# DAU_Kupplung_1_phasig_V1_13.net
KiCad netlist of a schematic drawn in EAGLE
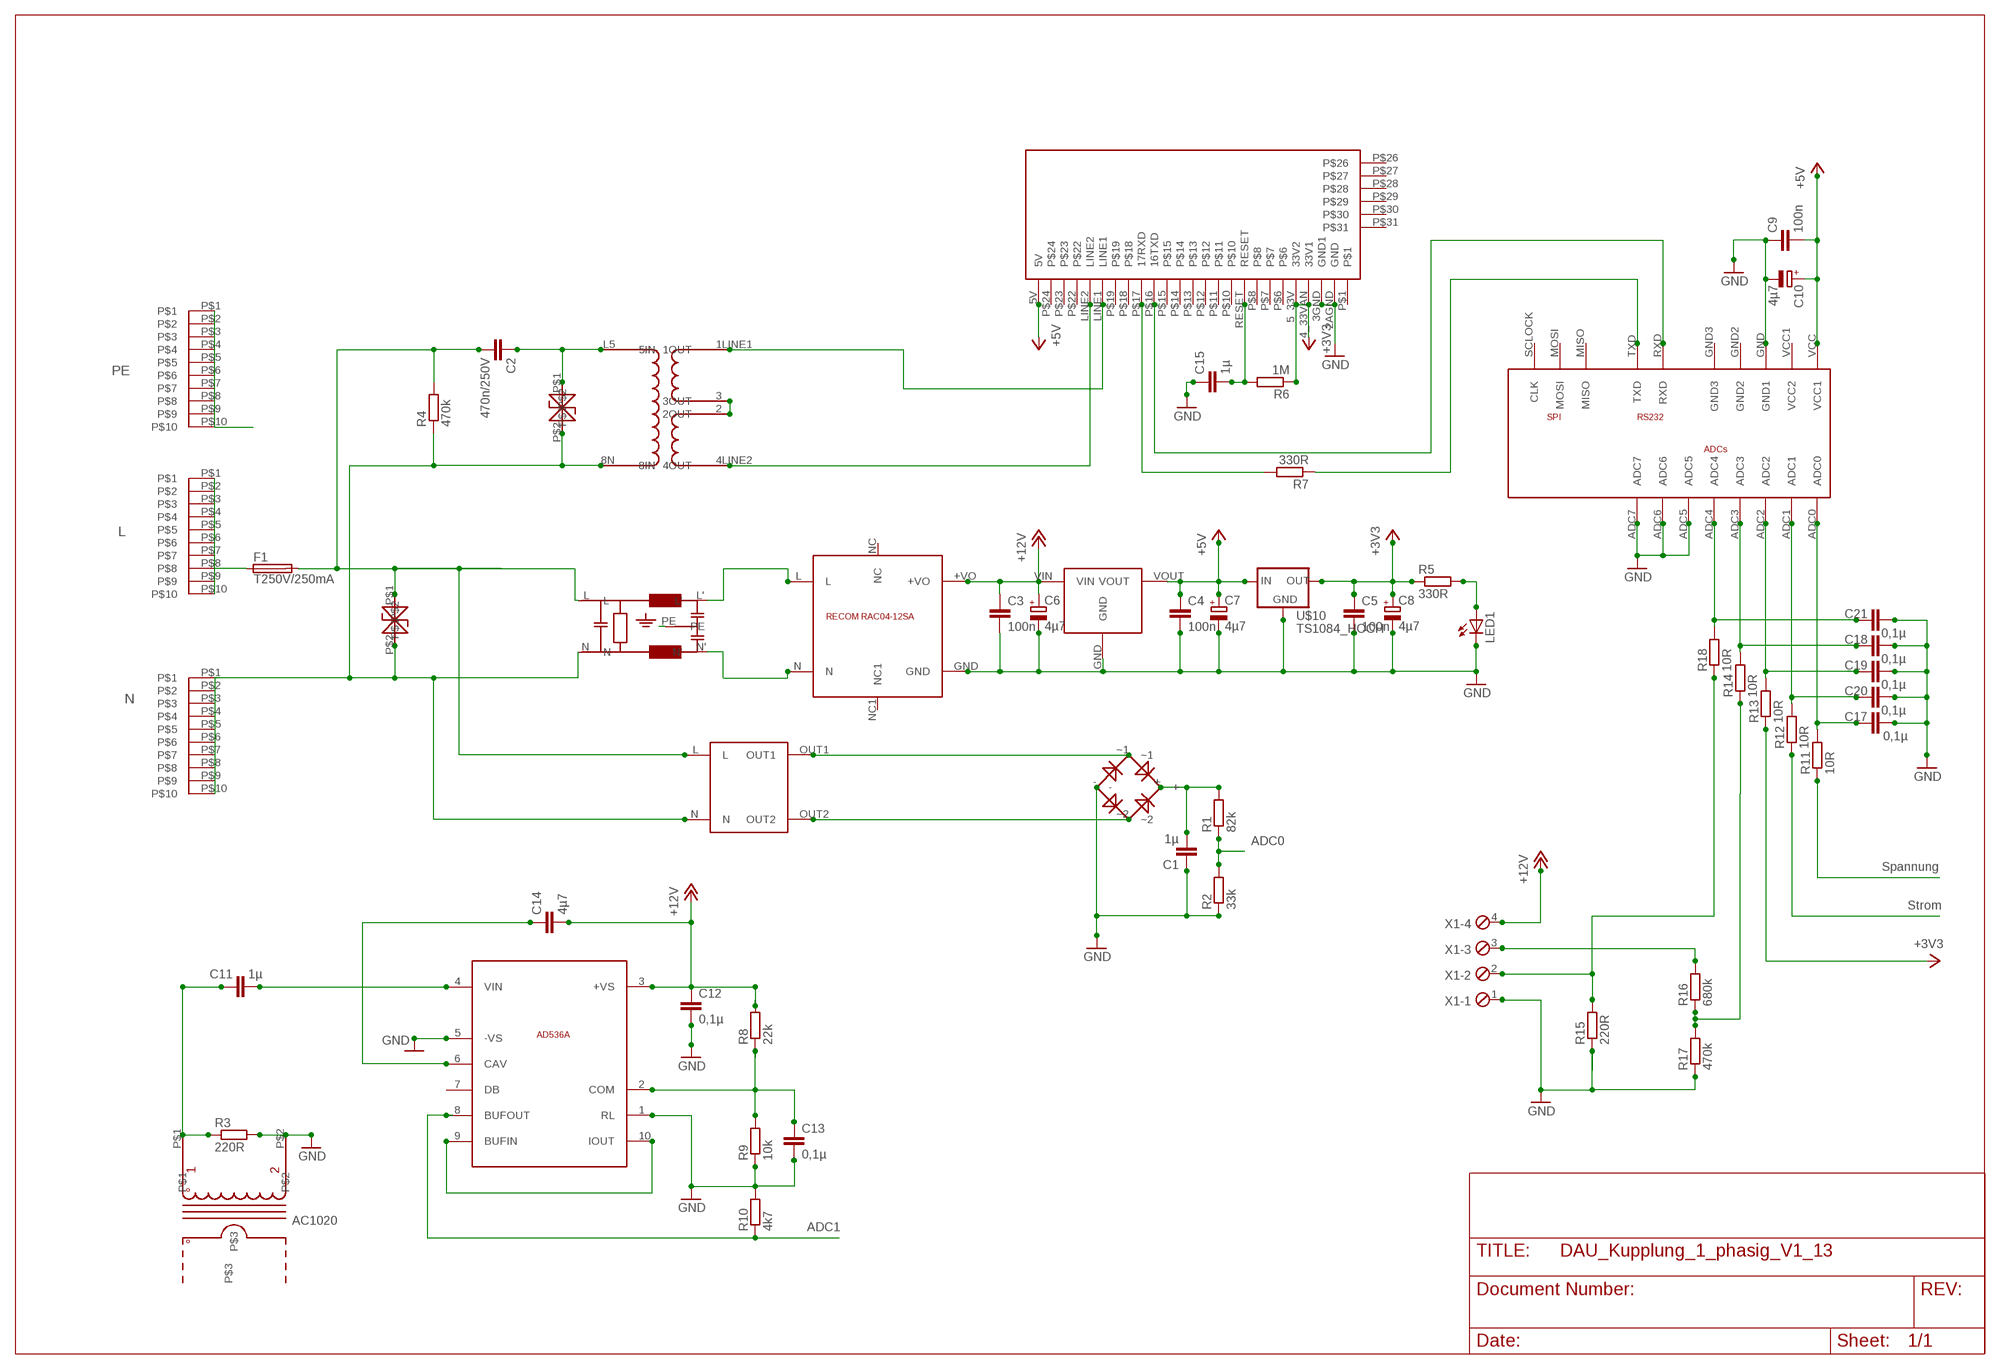
[diagram p0: schematic, sheet 1]

(export (version "E")
  (design (tool "Eeschema 10.0.6"))
  (components
    (comp (ref "AC1020")
      (value "AC1010")
      (footprint "eagle-import:AC1010")
      (libsource (lib "eagle-import") (part "AC1010"))
    )
    (comp (ref "C1")
      (value "1µ")
      (footprint "eagle-import:C2.5-3")
      (libsource (lib "eagle-import") (part "C2,5-3"))
    )
    (comp (ref "C2")
      (value "470n/250V")
      (footprint "eagle-import:C150-072X183")
      (libsource (lib "eagle-import") (part "resistor_C-EU150-072X183"))
    )
    (comp (ref "C3")
      (value "100n")
      (footprint "eagle-import:C0805")
      (libsource (lib "eagle-import") (part "resistor_C-EUC0805"))
    )
    (comp (ref "C4")
      (value "100n")
      (footprint "eagle-import:C0805")
      (libsource (lib "eagle-import") (part "resistor_C-EUC0805"))
    )
    (comp (ref "C5")
      (value "100n")
      (footprint "eagle-import:C0805")
      (libsource (lib "eagle-import") (part "resistor_C-EUC0805"))
    )
    (comp (ref "C6")
      (value "4µ7")
      (footprint "eagle-import:E2-4")
      (libsource (lib "eagle-import") (part "CPOL-EUE2-4"))
    )
    (comp (ref "C7")
      (value "4µ7")
      (footprint "eagle-import:E2-4")
      (libsource (lib "eagle-import") (part "CPOL-EUE2-4"))
    )
    (comp (ref "C8")
      (value "4µ7")
      (footprint "eagle-import:E2-4")
      (libsource (lib "eagle-import") (part "CPOL-EUE2-4"))
    )
    (comp (ref "C9")
      (value "100n")
      (footprint "eagle-import:C0805")
      (libsource (lib "eagle-import") (part "C-EUC0805"))
    )
    (comp (ref "C10")
      (value "4µ7")
      (footprint "eagle-import:E2-4")
      (libsource (lib "eagle-import") (part "CPOL-EUE2-4"))
    )
    (comp (ref "C11")
      (value "1µ")
      (footprint "eagle-import:C0805")
      (libsource (lib "eagle-import") (part "C-EUC0805"))
    )
    (comp (ref "C12")
      (value "0,1µ")
      (footprint "eagle-import:C0805")
      (libsource (lib "eagle-import") (part "C-EUC0805"))
    )
    (comp (ref "C13")
      (value "0,1µ")
      (footprint "eagle-import:C0805")
      (libsource (lib "eagle-import") (part "C-EUC0805"))
    )
    (comp (ref "C14")
      (value "4µ7")
      (footprint "eagle-import:C0805")
      (libsource (lib "eagle-import") (part "C-EUC0805"))
    )
    (comp (ref "C15")
      (value "1µ")
      (footprint "eagle-import:C0805")
      (libsource (lib "eagle-import") (part "resistor_C-EUC0805"))
    )
    (comp (ref "C17")
      (value "0,1µ")
      (footprint "eagle-import:C0805")
      (libsource (lib "eagle-import") (part "resistor_C-EUC0805"))
    )
    (comp (ref "C18")
      (value "0,1µ")
      (footprint "eagle-import:C0805")
      (libsource (lib "eagle-import") (part "resistor_C-EUC0805"))
    )
    (comp (ref "C19")
      (value "0,1µ")
      (footprint "eagle-import:C0805")
      (libsource (lib "eagle-import") (part "resistor_C-EUC0805"))
    )
    (comp (ref "C20")
      (value "0,1µ")
      (footprint "eagle-import:C0805")
      (libsource (lib "eagle-import") (part "resistor_C-EUC0805"))
    )
    (comp (ref "C21")
      (value "0,1µ")
      (footprint "eagle-import:C0805")
      (libsource (lib "eagle-import") (part "resistor_C-EUC0805"))
    )
    (comp (ref "F1")
      (value "T250V/250mA")
      (footprint "eagle-import:TR5")
      (libsource (lib "eagle-import") (part "TR5"))
    )
    (comp (ref "L")
      (value "PRINT_CONNECTOR")
      (footprint "eagle-import:FASTON_DOUBLE")
      (libsource (lib "eagle-import") (part "PRINT_CONNECTOR"))
    )
    (comp (ref "LED1")
      (value "LEDSQR2X5")
      (footprint "eagle-import:LED2X5")
      (libsource (lib "eagle-import") (part "LEDSQR2X5"))
    )
    (comp (ref "N")
      (value "PRINT_CONNECTOR")
      (footprint "eagle-import:FASTON_DOUBLE")
      (libsource (lib "eagle-import") (part "PRINT_CONNECTOR"))
    )
    (comp (ref "PE")
      (value "PRINT_CONNECTOR")
      (footprint "eagle-import:FASTON_DOUBLE")
      (libsource (lib "eagle-import") (part "PRINT_CONNECTOR"))
    )
    (comp (ref "R1")
      (value "82k")
      (footprint "eagle-import:R1206")
      (libsource (lib "eagle-import") (part "R-EU_R1206"))
    )
    (comp (ref "R2")
      (value "33k")
      (footprint "eagle-import:R1206")
      (libsource (lib "eagle-import") (part "R-EU_R1206"))
    )
    (comp (ref "R3")
      (value "220R")
      (footprint "eagle-import:R1206")
      (libsource (lib "eagle-import") (part "R-EU_R1206"))
    )
    (comp (ref "R4")
      (value "470k")
      (footprint "eagle-import:0204_7")
      (libsource (lib "eagle-import") (part "R-EU_0204/7"))
    )
    (comp (ref "R5")
      (value "330R")
      (footprint "eagle-import:R1206")
      (libsource (lib "eagle-import") (part "R-EU_R1206"))
    )
    (comp (ref "R6")
      (value "1M")
      (footprint "eagle-import:R1206")
      (libsource (lib "eagle-import") (part "R-EU_R1206"))
    )
    (comp (ref "R7")
      (value "330R")
      (footprint "eagle-import:R1206")
      (libsource (lib "eagle-import") (part "R-EU_R1206"))
    )
    (comp (ref "R8")
      (value "22k")
      (footprint "eagle-import:R1206")
      (libsource (lib "eagle-import") (part "R-EU_R1206"))
    )
    (comp (ref "R9")
      (value "10k")
      (footprint "eagle-import:R1206")
      (libsource (lib "eagle-import") (part "R-EU_R1206"))
    )
    (comp (ref "R10")
      (value "4k7")
      (footprint "eagle-import:R1206")
      (libsource (lib "eagle-import") (part "R-EU_R1206"))
    )
    (comp (ref "R11")
      (value "10R")
      (footprint "eagle-import:R1206")
      (libsource (lib "eagle-import") (part "R-EU_R1206"))
    )
    (comp (ref "R12")
      (value "10R")
      (footprint "eagle-import:R1206")
      (libsource (lib "eagle-import") (part "R-EU_R1206"))
    )
    (comp (ref "R13")
      (value "10R")
      (footprint "eagle-import:R1206")
      (libsource (lib "eagle-import") (part "R-EU_R1206"))
    )
    (comp (ref "R14")
      (value "10R")
      (footprint "eagle-import:R1206")
      (libsource (lib "eagle-import") (part "R-EU_R1206"))
    )
    (comp (ref "R15")
      (value "220R")
      (footprint "eagle-import:R1206")
      (libsource (lib "eagle-import") (part "R-EU_R1206"))
    )
    (comp (ref "R16")
      (value "680k")
      (footprint "eagle-import:R1206")
      (libsource (lib "eagle-import") (part "R-EU_R1206"))
    )
    (comp (ref "R17")
      (value "470k")
      (footprint "eagle-import:R1206")
      (libsource (lib "eagle-import") (part "R-EU_R1206"))
    )
    (comp (ref "R18")
      (value "10R")
      (footprint "eagle-import:R1206")
      (libsource (lib "eagle-import") (part "R-EU_R1206"))
    )
    (comp (ref "U$1")
      (value "RECOM_RAC04_12SA")
      (footprint "eagle-import:RAC04_12SA")
      (libsource (lib "eagle-import") (part "RECOM_RAC04_12SA"))
    )
    (comp (ref "U$2")
      (value "SICHERHEITSTRAFO")
      (footprint "eagle-import:TRAFO_0,35VA")
      (libsource (lib "eagle-import") (part "SICHERHEITSTRAFO"))
    )
    (comp (ref "U$3")
      (value "ADUC831_MINIMUM")
      (footprint "eagle-import:ADUC_MINIMUM")
      (libsource (lib "eagle-import") (part "ADUC831_MINIMUM"))
    )
    (comp (ref "U$4")
      (value "IT800")
      (footprint "eagle-import:IT800")
      (libsource (lib "eagle-import") (part "IT800"))
    )
    (comp (ref "U$5")
      (value "PLC_UEBERTRAGER_V2")
      (footprint "eagle-import:PLC-UEBERTRAGER_V2")
      (libsource (lib "eagle-import") (part "PLC_UEBERTRAGER_V2"))
    )
    (comp (ref "U$6")
      (value "NETZFILTER_05_A")
      (footprint "eagle-import:NETZFILTER")
      (libsource (lib "eagle-import") (part "NETZFILTER_05_A"))
    )
    (comp (ref "U$7")
      (value "AD536")
      (footprint "eagle-import:TO100_10PIN")
      (libsource (lib "eagle-import") (part "AD536"))
    )
    (comp (ref "U$8")
      (value "RECTIFIER")
      (footprint "eagle-import:RECTIFIER")
      (libsource (lib "eagle-import") (part "RECTIFIER"))
    )
    (comp (ref "U$9")
      (value "TSV")
      (footprint "eagle-import:TSV")
      (libsource (lib "eagle-import") (part "TSV"))
    )
    (comp (ref "U$10")
      (value "TS1084_HOCH")
      (footprint "eagle-import:TS1084_HOCH")
      (libsource (lib "eagle-import") (part "TS1084_HOCH"))
    )
    (comp (ref "U$11")
      (value "RECOM_785_05")
      (footprint "eagle-import:RECOM785X")
      (libsource (lib "eagle-import") (part "RECOM_785_05"))
    )
    (comp (ref "U$12")
      (value "TSV")
      (footprint "eagle-import:TSV")
      (libsource (lib "eagle-import") (part "TSV"))
    )
    (comp (ref "X1")
      (value "MPT4")
      (footprint "eagle-import:4POL254")
      (libsource (lib "eagle-import") (part "MPT4"))
    )
  )
  (nets
    (net (code "1") (name "+3V3") (class "Default")
      (node (ref "C5") (pin "1") (pinfunction "1_1") (pintype "passive"))
      (node (ref "C8") (pin "+") (pinfunction "+_+") (pintype "passive"))
      (node (ref "R13") (pin "1") (pinfunction "1_1") (pintype "passive"))
      (node (ref "R5") (pin "1") (pinfunction "1_1") (pintype "passive"))
      (node (ref "R6") (pin "1") (pinfunction "1_1") (pintype "passive"))
      (node (ref "U$10") (pin "OUT") (pinfunction "OUT_OUT") (pintype "passive"))
      (node (ref "U$4") (pin "4_33VAN") (pinfunction "33V1_4_33VAN") (pintype "bidirectional"))
      (node (ref "U$4") (pin "5_33V") (pinfunction "33V2_5_33V") (pintype "bidirectional"))
    )
    (net (code "2") (name "+5V") (class "Default")
      (node (ref "C10") (pin "+") (pinfunction "+_+") (pintype "passive"))
      (node (ref "C4") (pin "1") (pinfunction "1_1") (pintype "passive"))
      (node (ref "C7") (pin "+") (pinfunction "+_+") (pintype "passive"))
      (node (ref "C9") (pin "2") (pinfunction "2_2") (pintype "passive"))
      (node (ref "U$10") (pin "IN") (pinfunction "IN_IN") (pintype "input"))
      (node (ref "U$11") (pin "VOUT") (pinfunction "VOUT_VOUT") (pintype "bidirectional"))
      (node (ref "U$3") (pin "VCC") (pinfunction "VCC1_VCC") (pintype "bidirectional"))
      (node (ref "U$4") (pin "5V") (pinfunction "5V_5V") (pintype "bidirectional"))
    )
    (net (code "3") (name "+12V") (class "Default")
      (node (ref "C12") (pin "1") (pinfunction "1_1") (pintype "passive"))
      (node (ref "C14") (pin "2") (pinfunction "2_2") (pintype "passive"))
      (node (ref "C3") (pin "1") (pinfunction "1_1") (pintype "passive"))
      (node (ref "C6") (pin "+") (pinfunction "+_+") (pintype "passive"))
      (node (ref "R8") (pin "2") (pinfunction "2_2") (pintype "passive"))
      (node (ref "U$1") (pin "+VO") (pinfunction "+VO_+VO") (pintype "bidirectional"))
      (node (ref "U$11") (pin "VIN") (pinfunction "VIN_VIN") (pintype "bidirectional"))
      (node (ref "U$7") (pin "3") (pinfunction "+VS_3") (pintype "bidirectional"))
      (node (ref "X1") (pin "4") (pinfunction "1_4") (pintype "passive"))
    )
    (net (code "4") (name "/ADC0") (class "Default")
      (node (ref "R1") (pin "1") (pinfunction "1_1") (pintype "passive"))
      (node (ref "R11") (pin "1") (pinfunction "1_1") (pintype "passive"))
      (node (ref "R2") (pin "2") (pinfunction "2_2") (pintype "passive"))
    )
    (net (code "5") (name "/ADC1") (class "Default")
      (node (ref "R10") (pin "1") (pinfunction "1_1") (pintype "passive"))
      (node (ref "R12") (pin "1") (pinfunction "1_1") (pintype "passive"))
      (node (ref "U$7") (pin "8") (pinfunction "BUFOUT_8") (pintype "bidirectional"))
    )
    (net (code "6") (name "/PE") (class "Default")
      (node (ref "PE") (pin "P$1") (pinfunction "P$1_P$1") (pintype "bidirectional"))
      (node (ref "PE") (pin "P$10") (pinfunction "P$10_P$10") (pintype "bidirectional"))
      (node (ref "PE") (pin "P$2") (pinfunction "P$2_P$2") (pintype "bidirectional"))
      (node (ref "PE") (pin "P$3") (pinfunction "P$3_P$3") (pintype "bidirectional"))
      (node (ref "PE") (pin "P$4") (pinfunction "P$4_P$4") (pintype "bidirectional"))
      (node (ref "PE") (pin "P$5") (pinfunction "P$5_P$5") (pintype "bidirectional"))
      (node (ref "PE") (pin "P$6") (pinfunction "P$6_P$6") (pintype "bidirectional"))
      (node (ref "PE") (pin "P$7") (pinfunction "P$7_P$7") (pintype "bidirectional"))
      (node (ref "PE") (pin "P$8") (pinfunction "P$8_P$8") (pintype "bidirectional"))
      (node (ref "PE") (pin "P$9") (pinfunction "P$9_P$9") (pintype "bidirectional"))
      (node (ref "U$6") (pin "PE") (pinfunction "PE_PE") (pintype "input"))
    )
    (net (code "7") (name "GND") (class "Default")
      (node (ref "AC1020") (pin "P$2") (pinfunction "P$2_P$2") (pintype "bidirectional"))
      (node (ref "C1") (pin "1") (pinfunction "1_1") (pintype "passive"))
      (node (ref "C10") (pin "-") (pinfunction "-_-") (pintype "passive"))
      (node (ref "C12") (pin "2") (pinfunction "2_2") (pintype "passive"))
      (node (ref "C13") (pin "2") (pinfunction "2_2") (pintype "passive"))
      (node (ref "C15") (pin "1") (pinfunction "1_1") (pintype "passive"))
      (node (ref "C17") (pin "2") (pinfunction "2_2") (pintype "passive"))
      (node (ref "C18") (pin "2") (pinfunction "2_2") (pintype "passive"))
      (node (ref "C19") (pin "2") (pinfunction "2_2") (pintype "passive"))
      (node (ref "C20") (pin "2") (pinfunction "2_2") (pintype "passive"))
      (node (ref "C21") (pin "2") (pinfunction "2_2") (pintype "passive"))
      (node (ref "C3") (pin "2") (pinfunction "2_2") (pintype "passive"))
      (node (ref "C4") (pin "2") (pinfunction "2_2") (pintype "passive"))
      (node (ref "C5") (pin "2") (pinfunction "2_2") (pintype "passive"))
      (node (ref "C6") (pin "-") (pinfunction "-_-") (pintype "passive"))
      (node (ref "C7") (pin "-") (pinfunction "-_-") (pintype "passive"))
      (node (ref "C8") (pin "-") (pinfunction "-_-") (pintype "passive"))
      (node (ref "C9") (pin "1") (pinfunction "1_1") (pintype "passive"))
      (node (ref "LED1") (pin "K") (pinfunction "C_K") (pintype "passive"))
      (node (ref "R10") (pin "2") (pinfunction "2_2") (pintype "passive"))
      (node (ref "R15") (pin "1") (pinfunction "1_1") (pintype "passive"))
      (node (ref "R17") (pin "1") (pinfunction "1_1") (pintype "passive"))
      (node (ref "R2") (pin "1") (pinfunction "1_1") (pintype "passive"))
      (node (ref "R3") (pin "2") (pinfunction "2_2") (pintype "passive"))
      (node (ref "R9") (pin "1") (pinfunction "1_1") (pintype "passive"))
      (node (ref "U$1") (pin "GND") (pinfunction "GND_GND") (pintype "bidirectional"))
      (node (ref "U$10") (pin "GND") (pinfunction "GND_GND") (pintype "input"))
      (node (ref "U$11") (pin "GND") (pinfunction "GND_GND") (pintype "bidirectional"))
      (node (ref "U$3") (pin "ADC5") (pinfunction "ADC5_ADC5") (pintype "bidirectional"))
      (node (ref "U$3") (pin "ADC6") (pinfunction "ADC6_ADC6") (pintype "bidirectional"))
      (node (ref "U$3") (pin "ADC7") (pinfunction "ADC7_ADC7") (pintype "bidirectional"))
      (node (ref "U$3") (pin "GND") (pinfunction "GND1_GND") (pintype "bidirectional"))
      (node (ref "U$4") (pin "2AGND") (pinfunction "GND_2AGND") (pintype "bidirectional"))
      (node (ref "U$4") (pin "3GND") (pinfunction "GND1_3GND") (pintype "bidirectional"))
      (node (ref "U$7") (pin "1") (pinfunction "RL_1") (pintype "bidirectional"))
      (node (ref "U$7") (pin "5") (pinfunction "-VS_5") (pintype "bidirectional"))
      (node (ref "U$8") (pin "-") (pinfunction "-_-") (pintype "bidirectional"))
      (node (ref "X1") (pin "1") (pinfunction "1_1") (pintype "passive"))
    )
    (net (code "8") (name "Net-(AC1020-PadP$1)") (class "Default")
      (node (ref "AC1020") (pin "P$1") (pinfunction "P$1_P$1") (pintype "bidirectional"))
      (node (ref "C11") (pin "1") (pinfunction "1_1") (pintype "passive"))
      (node (ref "R3") (pin "1") (pinfunction "1_1") (pintype "passive"))
    )
    (net (code "9") (name "Net-(C1-Pad2)") (class "Default")
      (node (ref "C1") (pin "2") (pinfunction "2_2") (pintype "passive"))
      (node (ref "R1") (pin "2") (pinfunction "2_2") (pintype "passive"))
      (node (ref "U$8") (pin "+") (pinfunction "+_+") (pintype "bidirectional"))
    )
    (net (code "10") (name "Net-(C2-Pad2)") (class "Default")
      (node (ref "C2") (pin "2") (pinfunction "2_2") (pintype "passive"))
      (node (ref "F1") (pin "2") (pinfunction "2_2") (pintype "passive"))
      (node (ref "R4") (pin "2") (pinfunction "2_2") (pintype "passive"))
      (node (ref "U$2") (pin "L") (pinfunction "L_L") (pintype "bidirectional"))
      (node (ref "U$6") (pin "L") (pinfunction "L_L") (pintype "bidirectional"))
      (node (ref "U$9") (pin "P$1") (pinfunction "P$1_P$1") (pintype "bidirectional"))
    )
    (net (code "11") (name "Net-(C15-Pad2)") (class "Default")
      (node (ref "C15") (pin "2") (pinfunction "2_2") (pintype "passive"))
      (node (ref "R6") (pin "2") (pinfunction "2_2") (pintype "passive"))
      (node (ref "U$4") (pin "RESET") (pinfunction "RESET_RESET") (pintype "bidirectional"))
    )
    (net (code "12") (name "Net-(C17-Pad1)") (class "Default")
      (node (ref "C17") (pin "1") (pinfunction "1_1") (pintype "passive"))
      (node (ref "R11") (pin "2") (pinfunction "2_2") (pintype "passive"))
      (node (ref "U$3") (pin "ADC0") (pinfunction "ADC0_ADC0") (pintype "bidirectional"))
    )
    (net (code "13") (name "Net-(C18-Pad1)") (class "Default")
      (node (ref "C18") (pin "1") (pinfunction "1_1") (pintype "passive"))
      (node (ref "R14") (pin "2") (pinfunction "2_2") (pintype "passive"))
      (node (ref "U$3") (pin "ADC3") (pinfunction "ADC3_ADC3") (pintype "bidirectional"))
    )
    (net (code "14") (name "Net-(C19-Pad1)") (class "Default")
      (node (ref "C19") (pin "1") (pinfunction "1_1") (pintype "passive"))
      (node (ref "R13") (pin "2") (pinfunction "2_2") (pintype "passive"))
      (node (ref "U$3") (pin "ADC2") (pinfunction "ADC2_ADC2") (pintype "bidirectional"))
    )
    (net (code "15") (name "Net-(C20-Pad1)") (class "Default")
      (node (ref "C20") (pin "1") (pinfunction "1_1") (pintype "passive"))
      (node (ref "R12") (pin "2") (pinfunction "2_2") (pintype "passive"))
      (node (ref "U$3") (pin "ADC1") (pinfunction "ADC1_ADC1") (pintype "bidirectional"))
    )
    (net (code "16") (name "Net-(C21-Pad1)") (class "Default")
      (node (ref "C21") (pin "1") (pinfunction "1_1") (pintype "passive"))
      (node (ref "R18") (pin "2") (pinfunction "2_2") (pintype "passive"))
      (node (ref "U$3") (pin "ADC4") (pinfunction "ADC4_ADC4") (pintype "bidirectional"))
    )
    (net (code "17") (name "Net-(F1-Pad1)") (class "Default")
      (node (ref "F1") (pin "1") (pinfunction "1_1") (pintype "passive"))
      (node (ref "L") (pin "P$1") (pinfunction "P$1_P$1") (pintype "bidirectional"))
      (node (ref "L") (pin "P$10") (pinfunction "P$10_P$10") (pintype "bidirectional"))
      (node (ref "L") (pin "P$2") (pinfunction "P$2_P$2") (pintype "bidirectional"))
      (node (ref "L") (pin "P$3") (pinfunction "P$3_P$3") (pintype "bidirectional"))
      (node (ref "L") (pin "P$4") (pinfunction "P$4_P$4") (pintype "bidirectional"))
      (node (ref "L") (pin "P$5") (pinfunction "P$5_P$5") (pintype "bidirectional"))
      (node (ref "L") (pin "P$6") (pinfunction "P$6_P$6") (pintype "bidirectional"))
      (node (ref "L") (pin "P$7") (pinfunction "P$7_P$7") (pintype "bidirectional"))
      (node (ref "L") (pin "P$8") (pinfunction "P$8_P$8") (pintype "bidirectional"))
      (node (ref "L") (pin "P$9") (pinfunction "P$9_P$9") (pintype "bidirectional"))
    )
    (net (code "18") (name "Net-(LED1-PadA)") (class "Default")
      (node (ref "LED1") (pin "A") (pinfunction "A_A") (pintype "passive"))
      (node (ref "R5") (pin "2") (pinfunction "2_2") (pintype "passive"))
    )
    (net (code "19") (name "Net-(R7-Pad1)") (class "Default")
      (node (ref "R7") (pin "1") (pinfunction "1_1") (pintype "passive"))
      (node (ref "U$3") (pin "TXD") (pinfunction "TXD_TXD") (pintype "bidirectional"))
    )
    (net (code "20") (name "Net-(R14-Pad1)") (class "Default")
      (node (ref "R14") (pin "1") (pinfunction "1_1") (pintype "passive"))
      (node (ref "R16") (pin "1") (pinfunction "1_1") (pintype "passive"))
      (node (ref "R17") (pin "2") (pinfunction "2_2") (pintype "passive"))
    )
    (net (code "21") (name "Net-(U$1-PadL)") (class "Default")
      (node (ref "U$1") (pin "L") (pinfunction "L_L") (pintype "bidirectional"))
      (node (ref "U$6") (pin "L'") (pinfunction "L'_L'") (pintype "bidirectional"))
    )
    (net (code "22") (name "Net-(U$1-PadN)") (class "Default")
      (node (ref "U$1") (pin "N") (pinfunction "N_N") (pintype "bidirectional"))
      (node (ref "U$6") (pin "N'") (pinfunction "N'_N'") (pintype "bidirectional"))
    )
    (net (code "23") (name "Net-(U$4-16TXD)") (class "Default")
      (node (ref "U$3") (pin "RXD") (pinfunction "RXD_RXD") (pintype "bidirectional"))
      (node (ref "U$4") (pin "P$16") (pinfunction "16TXD_P$16") (pintype "bidirectional"))
    )
    (net (code "24") (name "Net-(U$4-17RXD)") (class "Default")
      (node (ref "R7") (pin "2") (pinfunction "2_2") (pintype "passive"))
      (node (ref "U$4") (pin "P$17") (pinfunction "17RXD_P$17") (pintype "bidirectional"))
    )
    (net (code "25") (name "Net-(U$5-1OUT)") (class "Default")
      (node (ref "U$4") (pin "LINE1") (pinfunction "LINE1_LINE1") (pintype "bidirectional"))
      (node (ref "U$5") (pin "1LINE1") (pinfunction "1OUT_1LINE1") (pintype "output"))
    )
    (net (code "26") (name "Net-(U$5-2OUT)") (class "Default")
      (node (ref "U$5") (pin "2") (pinfunction "2OUT_2") (pintype "output"))
      (node (ref "U$5") (pin "3") (pinfunction "3OUT_3") (pintype "output"))
    )
    (net (code "27") (name "Net-(U$5-4OUT)") (class "Default")
      (node (ref "U$4") (pin "LINE2") (pinfunction "LINE2_LINE2") (pintype "bidirectional"))
      (node (ref "U$5") (pin "4LINE2") (pinfunction "4OUT_4LINE2") (pintype "output"))
    )
    (net (code "28") (name "Net-(U$5-5IN)") (class "Default")
      (node (ref "C2") (pin "1") (pinfunction "1_1") (pintype "passive"))
      (node (ref "U$12") (pin "P$1") (pinfunction "P$1_P$1") (pintype "bidirectional"))
      (node (ref "U$5") (pin "L5") (pinfunction "5IN_L5") (pintype "input"))
    )
    (net (code "29") (name "Net-(U$5-8IN)") (class "Default")
      (node (ref "N") (pin "P$1") (pinfunction "P$1_P$1") (pintype "bidirectional"))
      (node (ref "N") (pin "P$10") (pinfunction "P$10_P$10") (pintype "bidirectional"))
      (node (ref "N") (pin "P$2") (pinfunction "P$2_P$2") (pintype "bidirectional"))
      (node (ref "N") (pin "P$3") (pinfunction "P$3_P$3") (pintype "bidirectional"))
      (node (ref "N") (pin "P$4") (pinfunction "P$4_P$4") (pintype "bidirectional"))
      (node (ref "N") (pin "P$5") (pinfunction "P$5_P$5") (pintype "bidirectional"))
      (node (ref "N") (pin "P$6") (pinfunction "P$6_P$6") (pintype "bidirectional"))
      (node (ref "N") (pin "P$7") (pinfunction "P$7_P$7") (pintype "bidirectional"))
      (node (ref "N") (pin "P$8") (pinfunction "P$8_P$8") (pintype "bidirectional"))
      (node (ref "N") (pin "P$9") (pinfunction "P$9_P$9") (pintype "bidirectional"))
      (node (ref "R4") (pin "1") (pinfunction "1_1") (pintype "passive"))
      (node (ref "U$12") (pin "P$2") (pinfunction "P$2_P$2") (pintype "bidirectional"))
      (node (ref "U$2") (pin "N") (pinfunction "N_N") (pintype "bidirectional"))
      (node (ref "U$5") (pin "8N") (pinfunction "8IN_8N") (pintype "input"))
      (node (ref "U$6") (pin "N") (pinfunction "N_N") (pintype "bidirectional"))
      (node (ref "U$9") (pin "P$2") (pinfunction "P$2_P$2") (pintype "bidirectional"))
    )
    (net (code "30") (name "Net-(U$7-BUFIN)") (class "Default")
      (node (ref "U$7") (pin "10") (pinfunction "IOUT_10") (pintype "bidirectional"))
      (node (ref "U$7") (pin "9") (pinfunction "BUFIN_9") (pintype "bidirectional"))
    )
    (net (code "31") (name "Net-(U$7-CAV)") (class "Default")
      (node (ref "C14") (pin "1") (pinfunction "1_1") (pintype "passive"))
      (node (ref "U$7") (pin "6") (pinfunction "CAV_6") (pintype "bidirectional"))
    )
    (net (code "32") (name "Net-(U$7-COM)") (class "Default")
      (node (ref "C13") (pin "1") (pinfunction "1_1") (pintype "passive"))
      (node (ref "R8") (pin "1") (pinfunction "1_1") (pintype "passive"))
      (node (ref "R9") (pin "2") (pinfunction "2_2") (pintype "passive"))
      (node (ref "U$7") (pin "2") (pinfunction "COM_2") (pintype "bidirectional"))
    )
    (net (code "33") (name "Net-(U$7-VIN)") (class "Default")
      (node (ref "C11") (pin "2") (pinfunction "2_2") (pintype "passive"))
      (node (ref "U$7") (pin "4") (pinfunction "VIN_4") (pintype "bidirectional"))
    )
    (net (code "34") (name "Net-(U$8-~{1})") (class "Default")
      (node (ref "U$2") (pin "OUT1") (pinfunction "OUT1_OUT1") (pintype "bidirectional"))
      (node (ref "U$8") (pin "~1") (pinfunction "~{1}_~1") (pintype "bidirectional"))
    )
    (net (code "35") (name "Net-(U$8-~{2})") (class "Default")
      (node (ref "U$2") (pin "OUT2") (pinfunction "OUT2_OUT2") (pintype "bidirectional"))
      (node (ref "U$8") (pin "~2") (pinfunction "~{2}_~2") (pintype "bidirectional"))
    )
    (net (code "36") (name "Net-(X1B-1)") (class "Default")
      (node (ref "R15") (pin "2") (pinfunction "2_2") (pintype "passive"))
      (node (ref "R18") (pin "1") (pinfunction "1_1") (pintype "passive"))
      (node (ref "X1") (pin "2") (pinfunction "1_2") (pintype "passive"))
    )
    (net (code "37") (name "Net-(X1C-1)") (class "Default")
      (node (ref "R16") (pin "2") (pinfunction "2_2") (pintype "passive"))
      (node (ref "X1") (pin "3") (pinfunction "1_3") (pintype "passive"))
    )
    (net (code "38") (name "unconnected-(AC1020-PadP$3)") (class "Default")
      (node (ref "AC1020") (pin "P$3") (pinfunction "P$3_P$3") (pintype "bidirectional"))
    )
    (net (code "39") (name "unconnected-(U$1-PadNC)") (class "Default")
      (node (ref "U$1") (pin "NC") (pinfunction "NC_NC") (pintype "bidirectional"))
    )
    (net (code "40") (name "unconnected-(U$1-PadNC1)") (class "Default")
      (node (ref "U$1") (pin "NC1") (pinfunction "NC1_NC1") (pintype "bidirectional"))
    )
    (net (code "41") (name "unconnected-(U$3-CLK-PadSCLOCK)") (class "Default")
      (node (ref "U$3") (pin "SCLOCK") (pinfunction "CLK_SCLOCK") (pintype "bidirectional"))
    )
    (net (code "42") (name "unconnected-(U$3-PadGND2)") (class "Default")
      (node (ref "U$3") (pin "GND2") (pinfunction "GND2_GND2") (pintype "bidirectional"))
    )
    (net (code "43") (name "unconnected-(U$3-PadGND3)") (class "Default")
      (node (ref "U$3") (pin "GND3") (pinfunction "GND3_GND3") (pintype "bidirectional"))
    )
    (net (code "44") (name "unconnected-(U$3-PadMISO)") (class "Default")
      (node (ref "U$3") (pin "MISO") (pinfunction "MISO_MISO") (pintype "bidirectional"))
    )
    (net (code "45") (name "unconnected-(U$3-PadMOSI)") (class "Default")
      (node (ref "U$3") (pin "MOSI") (pinfunction "MOSI_MOSI") (pintype "bidirectional"))
    )
    (net (code "46") (name "unconnected-(U$3-VCC2-PadVCC1)") (class "Default")
      (node (ref "U$3") (pin "VCC1") (pinfunction "VCC2_VCC1") (pintype "bidirectional"))
    )
    (net (code "47") (name "unconnected-(U$4-PadP$1)") (class "Default")
      (node (ref "U$4") (pin "P$1") (pinfunction "P$1_P$1") (pintype "bidirectional"))
    )
    (net (code "48") (name "unconnected-(U$4-PadP$6)") (class "Default")
      (node (ref "U$4") (pin "P$6") (pinfunction "P$6_P$6") (pintype "bidirectional"))
    )
    (net (code "49") (name "unconnected-(U$4-PadP$7)") (class "Default")
      (node (ref "U$4") (pin "P$7") (pinfunction "P$7_P$7") (pintype "bidirectional"))
    )
    (net (code "50") (name "unconnected-(U$4-PadP$8)") (class "Default")
      (node (ref "U$4") (pin "P$8") (pinfunction "P$8_P$8") (pintype "bidirectional"))
    )
    (net (code "51") (name "unconnected-(U$4-PadP$10)") (class "Default")
      (node (ref "U$4") (pin "P$10") (pinfunction "P$10_P$10") (pintype "bidirectional"))
    )
    (net (code "52") (name "unconnected-(U$4-PadP$11)") (class "Default")
      (node (ref "U$4") (pin "P$11") (pinfunction "P$11_P$11") (pintype "bidirectional"))
    )
    (net (code "53") (name "unconnected-(U$4-PadP$12)") (class "Default")
      (node (ref "U$4") (pin "P$12") (pinfunction "P$12_P$12") (pintype "bidirectional"))
    )
    (net (code "54") (name "unconnected-(U$4-PadP$13)") (class "Default")
      (node (ref "U$4") (pin "P$13") (pinfunction "P$13_P$13") (pintype "bidirectional"))
    )
    (net (code "55") (name "unconnected-(U$4-PadP$14)") (class "Default")
      (node (ref "U$4") (pin "P$14") (pinfunction "P$14_P$14") (pintype "bidirectional"))
    )
    (net (code "56") (name "unconnected-(U$4-PadP$15)") (class "Default")
      (node (ref "U$4") (pin "P$15") (pinfunction "P$15_P$15") (pintype "bidirectional"))
    )
    (net (code "57") (name "unconnected-(U$4-PadP$18)") (class "Default")
      (node (ref "U$4") (pin "P$18") (pinfunction "P$18_P$18") (pintype "bidirectional"))
    )
    (net (code "58") (name "unconnected-(U$4-PadP$19)") (class "Default")
      (node (ref "U$4") (pin "P$19") (pinfunction "P$19_P$19") (pintype "bidirectional"))
    )
    (net (code "59") (name "unconnected-(U$4-PadP$22)") (class "Default")
      (node (ref "U$4") (pin "P$22") (pinfunction "P$22_P$22") (pintype "bidirectional"))
    )
    (net (code "60") (name "unconnected-(U$4-PadP$23)") (class "Default")
      (node (ref "U$4") (pin "P$23") (pinfunction "P$23_P$23") (pintype "bidirectional"))
    )
    (net (code "61") (name "unconnected-(U$4-PadP$24)") (class "Default")
      (node (ref "U$4") (pin "P$24") (pinfunction "P$24_P$24") (pintype "bidirectional"))
    )
    (net (code "62") (name "unconnected-(U$4-PadP$26)") (class "Default")
      (node (ref "U$4") (pin "P$26") (pinfunction "P$26_P$26") (pintype "bidirectional"))
    )
    (net (code "63") (name "unconnected-(U$4-PadP$27)") (class "Default")
      (node (ref "U$4") (pin "P$27") (pinfunction "P$27_P$27") (pintype "bidirectional"))
    )
    (net (code "64") (name "unconnected-(U$4-PadP$28)") (class "Default")
      (node (ref "U$4") (pin "P$28") (pinfunction "P$28_P$28") (pintype "bidirectional"))
    )
    (net (code "65") (name "unconnected-(U$4-PadP$29)") (class "Default")
      (node (ref "U$4") (pin "P$29") (pinfunction "P$29_P$29") (pintype "bidirectional"))
    )
    (net (code "66") (name "unconnected-(U$4-PadP$30)") (class "Default")
      (node (ref "U$4") (pin "P$30") (pinfunction "P$30_P$30") (pintype "bidirectional"))
    )
    (net (code "67") (name "unconnected-(U$4-PadP$31)") (class "Default")
      (node (ref "U$4") (pin "P$31") (pinfunction "P$31_P$31") (pintype "bidirectional"))
    )
    (net (code "68") (name "unconnected-(U$7-DB-Pad7)") (class "Default")
      (node (ref "U$7") (pin "7") (pinfunction "DB_7") (pintype "bidirectional"))
    )
  )
)
